# System_Controll.net
KiCad netlist of a schematic drawn in EAGLE
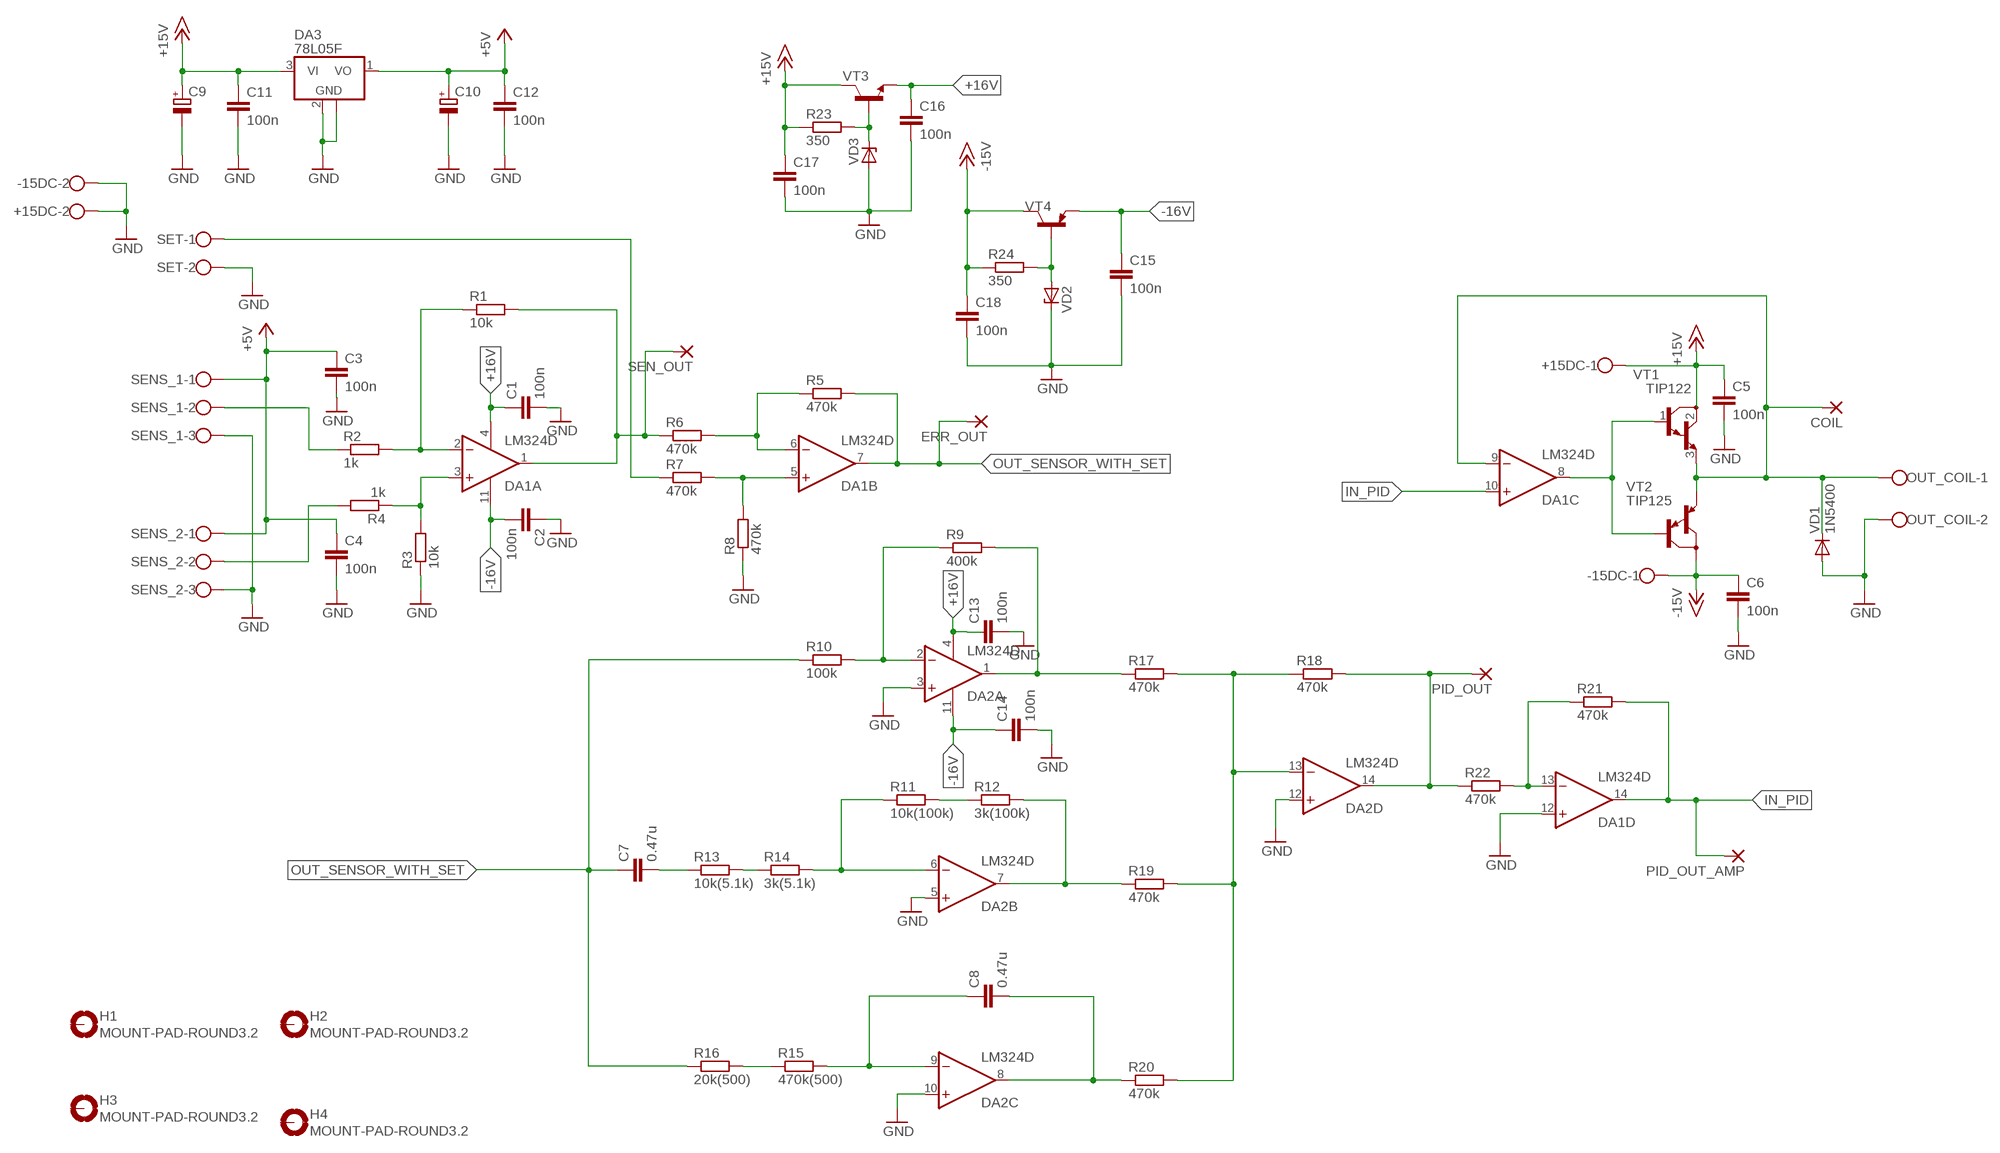
[diagram p0: schematic, sheet 1]

(export (version "E")
  (design (tool "Eeschema 10.0.6"))
  (components
    (comp (ref "+15DC")
      (value "W237-102")
      (footprint "eagle-import:W237-102")
      (fields (field (name "MPN") "237-102"))
      (libsource (lib "eagle-import") (part "W237-102"))
    )
    (comp (ref "-15DC")
      (value "W237-102")
      (footprint "eagle-import:W237-102")
      (fields (field (name "MPN") "237-102"))
      (libsource (lib "eagle-import") (part "W237-102"))
    )
    (comp (ref "C1")
      (value "100n")
      (footprint "eagle-import:C1206")
      (libsource (lib "eagle-import") (part "C-EUC1206"))
    )
    (comp (ref "C2")
      (value "100n")
      (footprint "eagle-import:C1206")
      (libsource (lib "eagle-import") (part "C-EUC1206"))
    )
    (comp (ref "C3")
      (value "100n")
      (footprint "eagle-import:C1206")
      (libsource (lib "eagle-import") (part "C-EUC1206"))
    )
    (comp (ref "C4")
      (value "100n")
      (footprint "eagle-import:C1206")
      (libsource (lib "eagle-import") (part "C-EUC1206"))
    )
    (comp (ref "C5")
      (value "100n")
      (footprint "eagle-import:C1206")
      (libsource (lib "eagle-import") (part "C-EUC1206"))
    )
    (comp (ref "C6")
      (value "100n")
      (footprint "eagle-import:C1206")
      (libsource (lib "eagle-import") (part "C-EUC1206"))
    )
    (comp (ref "C7")
      (value "0.47u")
      (footprint "eagle-import:C1206")
      (libsource (lib "eagle-import") (part "C-EUC1206"))
    )
    (comp (ref "C8")
      (value "0.47u")
      (footprint "eagle-import:C1206")
      (libsource (lib "eagle-import") (part "C-EUC1206"))
    )
    (comp (ref "C9")
      (value "CPOL-EUE2,5-6")
      (footprint "eagle-import:E2,5-6")
      (libsource (lib "eagle-import") (part "CPOL-EUE2,5-6"))
    )
    (comp (ref "C10")
      (value "CPOL-EUE2,5-6")
      (footprint "eagle-import:E2,5-6")
      (libsource (lib "eagle-import") (part "CPOL-EUE2,5-6"))
    )
    (comp (ref "C11")
      (value "100n")
      (footprint "eagle-import:C1206")
      (libsource (lib "eagle-import") (part "C-EUC1206"))
    )
    (comp (ref "C12")
      (value "100n")
      (footprint "eagle-import:C1206")
      (libsource (lib "eagle-import") (part "C-EUC1206"))
    )
    (comp (ref "C13")
      (value "100n")
      (footprint "eagle-import:C1206")
      (libsource (lib "eagle-import") (part "C-EUC1206"))
    )
    (comp (ref "C14")
      (value "100n")
      (footprint "eagle-import:C1206")
      (libsource (lib "eagle-import") (part "C-EUC1206"))
    )
    (comp (ref "C15")
      (value "100n")
      (footprint "eagle-import:C1206")
      (libsource (lib "eagle-import") (part "C-EUC1206"))
    )
    (comp (ref "C16")
      (value "100n")
      (footprint "eagle-import:C1206")
      (libsource (lib "eagle-import") (part "C-EUC1206"))
    )
    (comp (ref "C17")
      (value "100n")
      (footprint "eagle-import:C1206")
      (libsource (lib "eagle-import") (part "C-EUC1206"))
    )
    (comp (ref "C18")
      (value "100n")
      (footprint "eagle-import:C1206")
      (libsource (lib "eagle-import") (part "C-EUC1206"))
    )
    (comp (ref "COIL")
      (value "PW_PAD")
      (footprint "eagle-import:PW_PAD")
      (libsource (lib "eagle-import") (part "PW_PAD"))
    )
    (comp (ref "DA1")
      (value "LM324D")
      (footprint "eagle-import:SO14")
      (libsource (lib "eagle-import") (part "LM324D"))
    )
    (comp (ref "DA2")
      (value "LM324D")
      (footprint "eagle-import:SO14")
      (libsource (lib "eagle-import") (part "LM324D"))
    )
    (comp (ref "DA3")
      (value "78L05F")
      (footprint "eagle-import:SOT89")
      (libsource (lib "eagle-import") (part "78LF05"))
    )
    (comp (ref "ERR_OUT")
      (value "PW_PAD")
      (footprint "eagle-import:PW_PAD")
      (libsource (lib "eagle-import") (part "PW_PAD"))
    )
    (comp (ref "H1")
      (value "MOUNT-PAD-ROUND3.2")
      (footprint "eagle-import:3,2-PAD")
      (libsource (lib "eagle-import") (part "MOUNT-PAD-ROUND3.2"))
    )
    (comp (ref "H2")
      (value "MOUNT-PAD-ROUND3.2")
      (footprint "eagle-import:3,2-PAD")
      (libsource (lib "eagle-import") (part "MOUNT-PAD-ROUND3.2"))
    )
    (comp (ref "H3")
      (value "MOUNT-PAD-ROUND3.2")
      (footprint "eagle-import:3,2-PAD")
      (libsource (lib "eagle-import") (part "MOUNT-PAD-ROUND3.2"))
    )
    (comp (ref "H4")
      (value "MOUNT-PAD-ROUND3.2")
      (footprint "eagle-import:3,2-PAD")
      (libsource (lib "eagle-import") (part "MOUNT-PAD-ROUND3.2"))
    )
    (comp (ref "OUT_COIL")
      (value "DG350-3.5-02P")
      (footprint "eagle-import:DG350-3.5-02P")
      (fields (field (name "MPN") "237-102"))
      (libsource (lib "eagle-import") (part "DG350-3.5-02P"))
    )
    (comp (ref "PID_OUT")
      (value "PW_PAD")
      (footprint "eagle-import:PW_PAD")
      (libsource (lib "eagle-import") (part "PW_PAD"))
    )
    (comp (ref "PID_OUT_AMP")
      (value "PW_PAD")
      (footprint "eagle-import:PW_PAD")
      (libsource (lib "eagle-import") (part "PW_PAD"))
    )
    (comp (ref "R1")
      (value "10k")
      (footprint "eagle-import:M1206")
      (libsource (lib "eagle-import") (part "R-EUM1206"))
    )
    (comp (ref "R2")
      (value "1k")
      (footprint "eagle-import:M1206")
      (libsource (lib "eagle-import") (part "R-EUM1206"))
    )
    (comp (ref "R3")
      (value "10k")
      (footprint "eagle-import:M1206")
      (libsource (lib "eagle-import") (part "R-EUM1206"))
    )
    (comp (ref "R4")
      (value "1k")
      (footprint "eagle-import:M1206")
      (libsource (lib "eagle-import") (part "R-EUM1206"))
    )
    (comp (ref "R5")
      (value "470k")
      (footprint "eagle-import:M1206")
      (libsource (lib "eagle-import") (part "R-EUM1206"))
    )
    (comp (ref "R6")
      (value "470k")
      (footprint "eagle-import:M1206")
      (libsource (lib "eagle-import") (part "R-EUM1206"))
    )
    (comp (ref "R7")
      (value "470k")
      (footprint "eagle-import:M1206")
      (libsource (lib "eagle-import") (part "R-EUM1206"))
    )
    (comp (ref "R8")
      (value "470k")
      (footprint "eagle-import:M1206")
      (libsource (lib "eagle-import") (part "R-EUM1206"))
    )
    (comp (ref "R9")
      (value "400k")
      (footprint "eagle-import:M1206")
      (libsource (lib "eagle-import") (part "R-EUM1206"))
    )
    (comp (ref "R10")
      (value "100k")
      (footprint "eagle-import:M1206")
      (libsource (lib "eagle-import") (part "R-EUM1206"))
    )
    (comp (ref "R11")
      (value "10k(100k)")
      (footprint "eagle-import:M1206")
      (libsource (lib "eagle-import") (part "R-EUM1206"))
    )
    (comp (ref "R12")
      (value "3k(100k)")
      (footprint "eagle-import:M1206")
      (libsource (lib "eagle-import") (part "R-EUM1206"))
    )
    (comp (ref "R13")
      (value "10k(5.1k)")
      (footprint "eagle-import:M1206")
      (libsource (lib "eagle-import") (part "R-EUM1206"))
    )
    (comp (ref "R14")
      (value "3k(5.1k)")
      (footprint "eagle-import:M1206")
      (libsource (lib "eagle-import") (part "R-EUM1206"))
    )
    (comp (ref "R15")
      (value "470k(500)")
      (footprint "eagle-import:M1206")
      (libsource (lib "eagle-import") (part "R-EUM1206"))
    )
    (comp (ref "R16")
      (value "20k(500)")
      (footprint "eagle-import:M1206")
      (libsource (lib "eagle-import") (part "R-EUM1206"))
    )
    (comp (ref "R17")
      (value "470k")
      (footprint "eagle-import:M1206")
      (libsource (lib "eagle-import") (part "R-EUM1206"))
    )
    (comp (ref "R18")
      (value "470k")
      (footprint "eagle-import:M1206")
      (libsource (lib "eagle-import") (part "R-EUM1206"))
    )
    (comp (ref "R19")
      (value "470k")
      (footprint "eagle-import:M1206")
      (libsource (lib "eagle-import") (part "R-EUM1206"))
    )
    (comp (ref "R20")
      (value "470k")
      (footprint "eagle-import:M1206")
      (libsource (lib "eagle-import") (part "R-EUM1206"))
    )
    (comp (ref "R21")
      (value "470k")
      (footprint "eagle-import:M1206")
      (libsource (lib "eagle-import") (part "R-EUM1206"))
    )
    (comp (ref "R22")
      (value "470k")
      (footprint "eagle-import:M1206")
      (libsource (lib "eagle-import") (part "R-EUM1206"))
    )
    (comp (ref "R23")
      (value "350")
      (footprint "eagle-import:M1206")
      (libsource (lib "eagle-import") (part "R-EUM1206"))
    )
    (comp (ref "R24")
      (value "350")
      (footprint "eagle-import:M1206")
      (libsource (lib "eagle-import") (part "R-EUM1206"))
    )
    (comp (ref "SENS_1")
      (value "DG350-3.5-03P")
      (footprint "eagle-import:DG350-3.5-03P")
      (fields (field (name "MPN") "237-103"))
      (libsource (lib "eagle-import") (part "DG350-3.5-03P"))
    )
    (comp (ref "SENS_2")
      (value "DG350-3.5-03P")
      (footprint "eagle-import:DG350-3.5-03P")
      (fields (field (name "MPN") "237-103"))
      (libsource (lib "eagle-import") (part "DG350-3.5-03P"))
    )
    (comp (ref "SEN_OUT")
      (value "PW_PAD")
      (footprint "eagle-import:PW_PAD")
      (libsource (lib "eagle-import") (part "PW_PAD"))
    )
    (comp (ref "SET")
      (value "DG350-3.5-02P")
      (footprint "eagle-import:DG350-3.5-02P")
      (fields (field (name "MPN") "237-102"))
      (libsource (lib "eagle-import") (part "DG350-3.5-02P"))
    )
    (comp (ref "VD1")
      (value "1N5400")
      (footprint "eagle-import:DO201-15")
      (libsource (lib "eagle-import") (part "1N5400"))
    )
    (comp (ref "VD2")
      (value "ZENER-DIODEDO41Z10")
      (footprint "eagle-import:DO41Z10")
      (libsource (lib "eagle-import") (part "ZENER-DIODEDO41Z10"))
    )
    (comp (ref "VD3")
      (value "ZENER-DIODEDO41Z10")
      (footprint "eagle-import:DO41Z10")
      (libsource (lib "eagle-import") (part "ZENER-DIODEDO41Z10"))
    )
    (comp (ref "VT1")
      (value "TIP122")
      (footprint "eagle-import:TO220")
      (libsource (lib "eagle-import") (part "TIP122"))
    )
    (comp (ref "VT2")
      (value "TIP125")
      (footprint "eagle-import:TO220")
      (libsource (lib "eagle-import") (part "TIP125"))
    )
    (comp (ref "VT3")
      (value "BC847ALT1SMD")
      (footprint "eagle-import:SOT23")
      (libsource (lib "eagle-import") (part "BC847SMDALT1"))
    )
    (comp (ref "VT4")
      (value "BC807-16LT1SMD")
      (footprint "eagle-import:SOT23-BEC")
      (libsource (lib "eagle-import") (part "BC807SMD-16LT1"))
    )
  )
  (nets
    (net (code "1") (name "+5V") (class "Default")
      (node (ref "C10") (pin "+") (pinfunction "+_+") (pintype "passive"))
      (node (ref "C12") (pin "1") (pinfunction "1_1") (pintype "passive"))
      (node (ref "C3") (pin "1") (pinfunction "1_1") (pintype "passive"))
      (node (ref "C4") (pin "1") (pinfunction "1_1") (pintype "passive"))
      (node (ref "DA3") (pin "1") (pinfunction "VO_1") (pintype "passive"))
      (node (ref "SENS_1") (pin "1") (pinfunction "KL_1") (pintype "passive"))
      (node (ref "SENS_2") (pin "1") (pinfunction "KL_1") (pintype "passive"))
    )
    (net (code "2") (name "+15V") (class "Default")
      (node (ref "+15DC") (pin "1") (pinfunction "KL_1") (pintype "passive"))
      (node (ref "C11") (pin "1") (pinfunction "1_1") (pintype "passive"))
      (node (ref "C17") (pin "1") (pinfunction "1_1") (pintype "passive"))
      (node (ref "C5") (pin "1") (pinfunction "1_1") (pintype "passive"))
      (node (ref "C9") (pin "+") (pinfunction "+_+") (pintype "passive"))
      (node (ref "DA3") (pin "3") (pinfunction "VI_3") (pintype "input"))
      (node (ref "R23") (pin "1") (pinfunction "1_1") (pintype "passive"))
      (node (ref "VT1") (pin "2") (pinfunction "C_2") (pintype "passive"))
      (node (ref "VT3") (pin "3") (pinfunction "C_3") (pintype "passive"))
    )
    (net (code "3") (name "+16V") (class "Default")
      (node (ref "C1") (pin "1") (pinfunction "1_1") (pintype "passive"))
      (node (ref "C13") (pin "1") (pinfunction "1_1") (pintype "passive"))
      (node (ref "C16") (pin "1") (pinfunction "1_1") (pintype "passive"))
      (node (ref "DA1") (pin "4") (pinfunction "V+_4") (pintype "power_in"))
      (node (ref "DA2") (pin "4") (pinfunction "V+_4") (pintype "power_in"))
      (node (ref "VT3") (pin "2") (pinfunction "E_2") (pintype "passive"))
    )
    (net (code "4") (name "-15V") (class "Default")
      (node (ref "-15DC") (pin "1") (pinfunction "KL_1") (pintype "passive"))
      (node (ref "C18") (pin "1") (pinfunction "1_1") (pintype "passive"))
      (node (ref "C6") (pin "1") (pinfunction "1_1") (pintype "passive"))
      (node (ref "R24") (pin "1") (pinfunction "1_1") (pintype "passive"))
      (node (ref "VT2") (pin "2") (pinfunction "C_2") (pintype "passive"))
      (node (ref "VT4") (pin "C") (pinfunction "C_C") (pintype "passive"))
    )
    (net (code "5") (name "-16V") (class "Default")
      (node (ref "C14") (pin "1") (pinfunction "1_1") (pintype "passive"))
      (node (ref "C15") (pin "1") (pinfunction "1_1") (pintype "passive"))
      (node (ref "C2") (pin "2") (pinfunction "2_2") (pintype "passive"))
      (node (ref "DA1") (pin "11") (pinfunction "V-_11") (pintype "power_in"))
      (node (ref "DA2") (pin "11") (pinfunction "V-_11") (pintype "power_in"))
      (node (ref "VT4") (pin "E") (pinfunction "E_E") (pintype "passive"))
    )
    (net (code "6") (name "GND") (class "Default")
      (node (ref "+15DC") (pin "2") (pinfunction "KL_2") (pintype "passive"))
      (node (ref "-15DC") (pin "2") (pinfunction "KL_2") (pintype "passive"))
      (node (ref "C1") (pin "2") (pinfunction "2_2") (pintype "passive"))
      (node (ref "C10") (pin "-") (pinfunction "-_-") (pintype "passive"))
      (node (ref "C11") (pin "2") (pinfunction "2_2") (pintype "passive"))
      (node (ref "C12") (pin "2") (pinfunction "2_2") (pintype "passive"))
      (node (ref "C13") (pin "2") (pinfunction "2_2") (pintype "passive"))
      (node (ref "C14") (pin "2") (pinfunction "2_2") (pintype "passive"))
      (node (ref "C15") (pin "2") (pinfunction "2_2") (pintype "passive"))
      (node (ref "C16") (pin "2") (pinfunction "2_2") (pintype "passive"))
      (node (ref "C17") (pin "2") (pinfunction "2_2") (pintype "passive"))
      (node (ref "C18") (pin "2") (pinfunction "2_2") (pintype "passive"))
      (node (ref "C2") (pin "1") (pinfunction "1_1") (pintype "passive"))
      (node (ref "C3") (pin "2") (pinfunction "2_2") (pintype "passive"))
      (node (ref "C4") (pin "2") (pinfunction "2_2") (pintype "passive"))
      (node (ref "C5") (pin "2") (pinfunction "2_2") (pintype "passive"))
      (node (ref "C6") (pin "2") (pinfunction "2_2") (pintype "passive"))
      (node (ref "C9") (pin "-") (pinfunction "-_-") (pintype "passive"))
      (node (ref "DA1") (pin "12") (pinfunction "+IN_12") (pintype "input"))
      (node (ref "DA2") (pin "10") (pinfunction "+IN_10") (pintype "input"))
      (node (ref "DA2") (pin "12") (pinfunction "+IN_12") (pintype "input"))
      (node (ref "DA2") (pin "3") (pinfunction "+IN_3") (pintype "input"))
      (node (ref "DA2") (pin "5") (pinfunction "+IN_5") (pintype "input"))
      (node (ref "DA3") (pin "2") (pinfunction "GND_2") (pintype "passive"))
      (node (ref "DA3") (pin "2@1") (pinfunction "GND_2@1") (pintype "passive"))
      (node (ref "OUT_COIL") (pin "2") (pinfunction "KL_2") (pintype "passive"))
      (node (ref "R3") (pin "1") (pinfunction "1_1") (pintype "passive"))
      (node (ref "R8") (pin "1") (pinfunction "1_1") (pintype "passive"))
      (node (ref "SENS_1") (pin "3") (pinfunction "KL_3") (pintype "passive"))
      (node (ref "SENS_2") (pin "3") (pinfunction "KL_3") (pintype "passive"))
      (node (ref "SET") (pin "2") (pinfunction "KL_2") (pintype "passive"))
      (node (ref "VD1") (pin "A") (pinfunction "A_A") (pintype "passive"))
      (node (ref "VD2") (pin "C") (pinfunction "C_C") (pintype "passive"))
      (node (ref "VD3") (pin "A") (pinfunction "A_A") (pintype "passive"))
    )
    (net (code "7") (name "IN_PID") (class "Default")
      (node (ref "DA1") (pin "10") (pinfunction "+IN_10") (pintype "input"))
      (node (ref "DA1") (pin "14") (pinfunction "OUT_14") (pintype "output"))
      (node (ref "PID_OUT_AMP") (pin "P$1") (pinfunction "P_P$1") (pintype "passive"))
      (node (ref "R21") (pin "2") (pinfunction "2_2") (pintype "passive"))
    )
    (net (code "8") (name "Net-(C7-Pad2)") (class "Default")
      (node (ref "C7") (pin "2") (pinfunction "2_2") (pintype "passive"))
      (node (ref "R13") (pin "1") (pinfunction "1_1") (pintype "passive"))
    )
    (net (code "9") (name "Net-(COIL-P)") (class "Default")
      (node (ref "COIL") (pin "P$1") (pinfunction "P_P$1") (pintype "passive"))
      (node (ref "DA1") (pin "9") (pinfunction "-IN_9") (pintype "input"))
      (node (ref "OUT_COIL") (pin "1") (pinfunction "KL_1") (pintype "passive"))
      (node (ref "VD1") (pin "C") (pinfunction "C_C") (pintype "passive"))
      (node (ref "VT1") (pin "3") (pinfunction "E_3") (pintype "passive"))
      (node (ref "VT2") (pin "3") (pinfunction "E_3") (pintype "passive"))
    )
    (net (code "10") (name "Net-(DA1A-+IN)") (class "Default")
      (node (ref "DA1") (pin "3") (pinfunction "+IN_3") (pintype "input"))
      (node (ref "R3") (pin "2") (pinfunction "2_2") (pintype "passive"))
      (node (ref "R4") (pin "1") (pinfunction "1_1") (pintype "passive"))
    )
    (net (code "11") (name "Net-(DA1A--IN)") (class "Default")
      (node (ref "DA1") (pin "2") (pinfunction "-IN_2") (pintype "input"))
      (node (ref "R1") (pin "1") (pinfunction "1_1") (pintype "passive"))
      (node (ref "R2") (pin "2") (pinfunction "2_2") (pintype "passive"))
    )
    (net (code "12") (name "Net-(DA1A-OUT)") (class "Default")
      (node (ref "DA1") (pin "1") (pinfunction "OUT_1") (pintype "output"))
      (node (ref "R1") (pin "2") (pinfunction "2_2") (pintype "passive"))
      (node (ref "R6") (pin "1") (pinfunction "1_1") (pintype "passive"))
      (node (ref "SEN_OUT") (pin "P$1") (pinfunction "P_P$1") (pintype "passive"))
    )
    (net (code "13") (name "Net-(DA1B-+IN)") (class "Default")
      (node (ref "DA1") (pin "5") (pinfunction "+IN_5") (pintype "input"))
      (node (ref "R7") (pin "2") (pinfunction "2_2") (pintype "passive"))
      (node (ref "R8") (pin "2") (pinfunction "2_2") (pintype "passive"))
    )
    (net (code "14") (name "Net-(DA1B--IN)") (class "Default")
      (node (ref "DA1") (pin "6") (pinfunction "-IN_6") (pintype "input"))
      (node (ref "R5") (pin "1") (pinfunction "1_1") (pintype "passive"))
      (node (ref "R6") (pin "2") (pinfunction "2_2") (pintype "passive"))
    )
    (net (code "15") (name "Net-(DA1C-OUT)") (class "Default")
      (node (ref "DA1") (pin "8") (pinfunction "OUT_8") (pintype "output"))
      (node (ref "VT1") (pin "1") (pinfunction "B_1") (pintype "passive"))
      (node (ref "VT2") (pin "1") (pinfunction "B_1") (pintype "passive"))
    )
    (net (code "16") (name "Net-(DA1D--IN)") (class "Default")
      (node (ref "DA1") (pin "13") (pinfunction "-IN_13") (pintype "input"))
      (node (ref "R21") (pin "1") (pinfunction "1_1") (pintype "passive"))
      (node (ref "R22") (pin "2") (pinfunction "2_2") (pintype "passive"))
    )
    (net (code "17") (name "Net-(DA2A--IN)") (class "Default")
      (node (ref "DA2") (pin "2") (pinfunction "-IN_2") (pintype "input"))
      (node (ref "R10") (pin "2") (pinfunction "2_2") (pintype "passive"))
      (node (ref "R9") (pin "1") (pinfunction "1_1") (pintype "passive"))
    )
    (net (code "18") (name "Net-(DA2A-OUT)") (class "Default")
      (node (ref "DA2") (pin "1") (pinfunction "OUT_1") (pintype "output"))
      (node (ref "R17") (pin "1") (pinfunction "1_1") (pintype "passive"))
      (node (ref "R9") (pin "2") (pinfunction "2_2") (pintype "passive"))
    )
    (net (code "19") (name "Net-(DA2B--IN)") (class "Default")
      (node (ref "DA2") (pin "6") (pinfunction "-IN_6") (pintype "input"))
      (node (ref "R11") (pin "1") (pinfunction "1_1") (pintype "passive"))
      (node (ref "R14") (pin "2") (pinfunction "2_2") (pintype "passive"))
    )
    (net (code "20") (name "Net-(DA2B-OUT)") (class "Default")
      (node (ref "DA2") (pin "7") (pinfunction "OUT_7") (pintype "output"))
      (node (ref "R12") (pin "2") (pinfunction "2_2") (pintype "passive"))
      (node (ref "R19") (pin "1") (pinfunction "1_1") (pintype "passive"))
    )
    (net (code "21") (name "Net-(DA2C--IN)") (class "Default")
      (node (ref "C8") (pin "1") (pinfunction "1_1") (pintype "passive"))
      (node (ref "DA2") (pin "9") (pinfunction "-IN_9") (pintype "input"))
      (node (ref "R15") (pin "2") (pinfunction "2_2") (pintype "passive"))
    )
    (net (code "22") (name "Net-(DA2C-OUT)") (class "Default")
      (node (ref "C8") (pin "2") (pinfunction "2_2") (pintype "passive"))
      (node (ref "DA2") (pin "8") (pinfunction "OUT_8") (pintype "output"))
      (node (ref "R20") (pin "1") (pinfunction "1_1") (pintype "passive"))
    )
    (net (code "23") (name "Net-(DA2D--IN)") (class "Default")
      (node (ref "DA2") (pin "13") (pinfunction "-IN_13") (pintype "input"))
      (node (ref "R17") (pin "2") (pinfunction "2_2") (pintype "passive"))
      (node (ref "R18") (pin "1") (pinfunction "1_1") (pintype "passive"))
      (node (ref "R19") (pin "2") (pinfunction "2_2") (pintype "passive"))
      (node (ref "R20") (pin "2") (pinfunction "2_2") (pintype "passive"))
    )
    (net (code "24") (name "Net-(DA2D-OUT)") (class "Default")
      (node (ref "DA2") (pin "14") (pinfunction "OUT_14") (pintype "output"))
      (node (ref "PID_OUT") (pin "P$1") (pinfunction "P_P$1") (pintype "passive"))
      (node (ref "R18") (pin "2") (pinfunction "2_2") (pintype "passive"))
      (node (ref "R22") (pin "1") (pinfunction "1_1") (pintype "passive"))
    )
    (net (code "25") (name "Net-(R11-Pad2)") (class "Default")
      (node (ref "R11") (pin "2") (pinfunction "2_2") (pintype "passive"))
      (node (ref "R12") (pin "1") (pinfunction "1_1") (pintype "passive"))
    )
    (net (code "26") (name "Net-(R13-Pad2)") (class "Default")
      (node (ref "R13") (pin "2") (pinfunction "2_2") (pintype "passive"))
      (node (ref "R14") (pin "1") (pinfunction "1_1") (pintype "passive"))
    )
    (net (code "27") (name "Net-(R15-Pad1)") (class "Default")
      (node (ref "R15") (pin "1") (pinfunction "1_1") (pintype "passive"))
      (node (ref "R16") (pin "2") (pinfunction "2_2") (pintype "passive"))
    )
    (net (code "28") (name "Net-(R24-Pad2)") (class "Default")
      (node (ref "R24") (pin "2") (pinfunction "2_2") (pintype "passive"))
      (node (ref "VD2") (pin "A") (pinfunction "A_A") (pintype "passive"))
      (node (ref "VT4") (pin "B") (pinfunction "B_B") (pintype "passive"))
    )
    (net (code "29") (name "Net-(SENS_1B-KL)") (class "Default")
      (node (ref "R2") (pin "1") (pinfunction "1_1") (pintype "passive"))
      (node (ref "SENS_1") (pin "2") (pinfunction "KL_2") (pintype "passive"))
    )
    (net (code "30") (name "Net-(SENS_2B-KL)") (class "Default")
      (node (ref "R4") (pin "2") (pinfunction "2_2") (pintype "passive"))
      (node (ref "SENS_2") (pin "2") (pinfunction "KL_2") (pintype "passive"))
    )
    (net (code "31") (name "Net-(SETA-KL)") (class "Default")
      (node (ref "R7") (pin "1") (pinfunction "1_1") (pintype "passive"))
      (node (ref "SET") (pin "1") (pinfunction "KL_1") (pintype "passive"))
    )
    (net (code "32") (name "Net-(VT3-B)") (class "Default")
      (node (ref "R23") (pin "2") (pinfunction "2_2") (pintype "passive"))
      (node (ref "VD3") (pin "C") (pinfunction "C_C") (pintype "passive"))
      (node (ref "VT3") (pin "1") (pinfunction "B_1") (pintype "passive"))
    )
    (net (code "33") (name "OUT_SENSOR_WITH_SET") (class "Default")
      (node (ref "C7") (pin "1") (pinfunction "1_1") (pintype "passive"))
      (node (ref "DA1") (pin "7") (pinfunction "OUT_7") (pintype "output"))
      (node (ref "ERR_OUT") (pin "P$1") (pinfunction "P_P$1") (pintype "passive"))
      (node (ref "R10") (pin "1") (pinfunction "1_1") (pintype "passive"))
      (node (ref "R16") (pin "1") (pinfunction "1_1") (pintype "passive"))
      (node (ref "R5") (pin "2") (pinfunction "2_2") (pintype "passive"))
    )
    (net (code "34") (name "unconnected-(H1-MOUNT-PadB3,2)") (class "Default")
      (node (ref "H1") (pin "B3,2") (pinfunction "MOUNT_B3,2") (pintype "passive"))
    )
    (net (code "35") (name "unconnected-(H2-MOUNT-PadB3,2)") (class "Default")
      (node (ref "H2") (pin "B3,2") (pinfunction "MOUNT_B3,2") (pintype "passive"))
    )
    (net (code "36") (name "unconnected-(H3-MOUNT-PadB3,2)") (class "Default")
      (node (ref "H3") (pin "B3,2") (pinfunction "MOUNT_B3,2") (pintype "passive"))
    )
    (net (code "37") (name "unconnected-(H4-MOUNT-PadB3,2)") (class "Default")
      (node (ref "H4") (pin "B3,2") (pinfunction "MOUNT_B3,2") (pintype "passive"))
    )
  )
)
